# pPump1.net
KiCad netlist of a schematic drawn in EAGLE
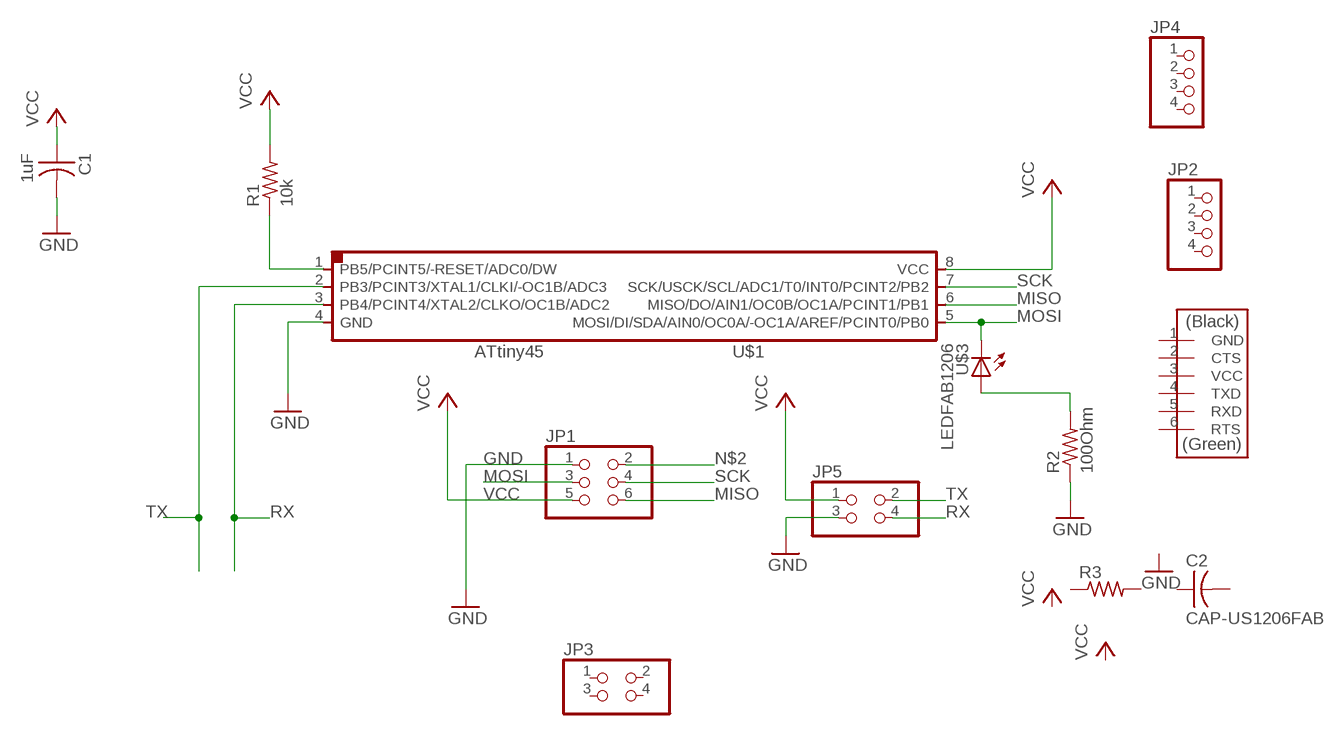
[diagram p0: schematic, sheet 1]

(export (version "E")
  (design (tool "Eeschema 10.0.6"))
  (components
    (comp (ref "C1")
      (value "1uF")
      (footprint "eagle-import:C1206FAB")
      (libsource (lib "eagle-import") (part "CAP-US1206FAB"))
    )
    (comp (ref "C2")
      (value "CAP-US1206FAB")
      (footprint "eagle-import:C1206FAB")
      (libsource (lib "eagle-import") (part "CAP-US1206FAB"))
    )
    (comp (ref "JP1")
      (value "PINHD-2X3-SMD")
      (footprint "eagle-import:2X03SMD")
      (libsource (lib "eagle-import") (part "PINHD-2X3-SMD"))
    )
    (comp (ref "JP2")
      (value "PINHD-1X4")
      (footprint "eagle-import:1X04")
      (libsource (lib "eagle-import") (part "PINHD-1X4"))
    )
    (comp (ref "JP3")
      (value "PINHD-2X2")
      (footprint "eagle-import:2X02")
      (libsource (lib "eagle-import") (part "PINHD-2X2"))
    )
    (comp (ref "JP4")
      (value "PINHD-1X4/90")
      (footprint "eagle-import:1X04_90")
      (libsource (lib "eagle-import") (part "PINHD-1X4/90"))
    )
    (comp (ref "JP5")
      (value "PINHD-2X02_2.54-SMD")
      (footprint "eagle-import:2X02SMD")
      (libsource (lib "eagle-import") (part "PINHD-2X02_2.54-SMD"))
    )
    (comp (ref "R1")
      (value "10k")
      (footprint "eagle-import:R1206FAB")
      (libsource (lib "eagle-import") (part "RES-US1206FAB"))
    )
    (comp (ref "R2")
      (value "100Ohm")
      (footprint "eagle-import:R1206FAB")
      (libsource (lib "eagle-import") (part "RES-US1206FAB"))
    )
    (comp (ref "R3")
      (value "RES-US1206FAB")
      (footprint "eagle-import:R1206FAB")
      (libsource (lib "eagle-import") (part "RES-US1206FAB"))
    )
    (comp (ref "U$1")
      (value "ATTINY45SI")
      (footprint "eagle-import:SOIC8")
      (libsource (lib "eagle-import") (part "ATTINY45SI"))
    )
    (comp (ref "U$2")
      (value "FTDI-SMD-HEADER")
      (footprint "eagle-import:1X06SMD")
      (libsource (lib "eagle-import") (part "FTDI-SMD-HEADER"))
    )
    (comp (ref "U$3")
      (value "LEDFAB1206")
      (footprint "eagle-import:LED1206FAB")
      (libsource (lib "eagle-import") (part "LEDFAB1206"))
    )
  )
  (nets
    (net (code "1") (name "/MISO") (class "Default")
      (node (ref "JP1") (pin "6") (pinfunction "6_6") (pintype "passive"))
      (node (ref "U$1") (pin "6") (pinfunction "MISO/DO/AIN1/OC0B/OC1A/PCINT1/PB1_6") (pintype "bidirectional"))
    )
    (net (code "2") (name "/MOSI") (class "Default")
      (node (ref "JP1") (pin "3") (pinfunction "3_3") (pintype "passive"))
      (node (ref "U$1") (pin "5") (pinfunction "MOSI/DI/SDA/AIN0/OC0A/-OC1A/AREF/PCINT0/PB0_5") (pintype "bidirectional"))
      (node (ref "U$3") (pin "2") (pinfunction "C_2") (pintype "passive"))
    )
    (net (code "3") (name "/N$2") (class "Default")
      (node (ref "JP1") (pin "2") (pinfunction "2_2") (pintype "passive"))
    )
    (net (code "4") (name "/RX") (class "Default")
      (node (ref "JP5") (pin "4") (pinfunction "4_4") (pintype "passive"))
      (node (ref "U$1") (pin "3") (pinfunction "PB4/PCINT4/XTAL2/CLKO/OC1B/ADC2_3") (pintype "bidirectional"))
    )
    (net (code "5") (name "/SCK") (class "Default")
      (node (ref "JP1") (pin "4") (pinfunction "4_4") (pintype "passive"))
      (node (ref "U$1") (pin "7") (pinfunction "SCK/USCK/SCL/ADC1/T0/INT0/PCINT2/PB2_7") (pintype "bidirectional"))
    )
    (net (code "6") (name "/TX") (class "Default")
      (node (ref "JP5") (pin "2") (pinfunction "2_2") (pintype "passive"))
      (node (ref "U$1") (pin "2") (pinfunction "PB3/PCINT3/XTAL1/CLKI/-OC1B/ADC3_2") (pintype "bidirectional"))
    )
    (net (code "7") (name "GND") (class "Default")
      (node (ref "C1") (pin "2") (pinfunction "2_2") (pintype "passive"))
      (node (ref "JP1") (pin "1") (pinfunction "1_1") (pintype "passive"))
      (node (ref "JP5") (pin "3") (pinfunction "3_3") (pintype "passive"))
      (node (ref "R2") (pin "1") (pinfunction "1_1") (pintype "passive"))
      (node (ref "U$1") (pin "4") (pinfunction "GND_4") (pintype "bidirectional"))
    )
    (net (code "8") (name "Net-(U$1-PB5{slash}PCINT5{slash}-RESET{slash}ADC0{slash}DW)") (class "Default")
      (node (ref "R1") (pin "1") (pinfunction "1_1") (pintype "passive"))
      (node (ref "U$1") (pin "1") (pinfunction "PB5/PCINT5/-RESET/ADC0/DW_1") (pintype "bidirectional"))
    )
    (net (code "9") (name "Net-(U$3-A)") (class "Default")
      (node (ref "R2") (pin "2") (pinfunction "2_2") (pintype "passive"))
      (node (ref "U$3") (pin "1") (pinfunction "A_1") (pintype "passive"))
    )
    (net (code "10") (name "VCC") (class "Default")
      (node (ref "C1") (pin "1") (pinfunction "1_1") (pintype "passive"))
      (node (ref "JP1") (pin "5") (pinfunction "5_5") (pintype "passive"))
      (node (ref "JP5") (pin "1") (pinfunction "1_1") (pintype "passive"))
      (node (ref "R1") (pin "2") (pinfunction "2_2") (pintype "passive"))
      (node (ref "U$1") (pin "8") (pinfunction "VCC_8") (pintype "bidirectional"))
    )
    (net (code "11") (name "unconnected-(C2-Pad1)") (class "Default")
      (node (ref "C2") (pin "1") (pinfunction "1_1") (pintype "passive"))
    )
    (net (code "12") (name "unconnected-(C2-Pad2)") (class "Default")
      (node (ref "C2") (pin "2") (pinfunction "2_2") (pintype "passive"))
    )
    (net (code "13") (name "unconnected-(JP2-Pad1)") (class "Default")
      (node (ref "JP2") (pin "1") (pinfunction "1_1") (pintype "passive"))
    )
    (net (code "14") (name "unconnected-(JP2-Pad2)") (class "Default")
      (node (ref "JP2") (pin "2") (pinfunction "2_2") (pintype "passive"))
    )
    (net (code "15") (name "unconnected-(JP2-Pad3)") (class "Default")
      (node (ref "JP2") (pin "3") (pinfunction "3_3") (pintype "passive"))
    )
    (net (code "16") (name "unconnected-(JP2-Pad4)") (class "Default")
      (node (ref "JP2") (pin "4") (pinfunction "4_4") (pintype "passive"))
    )
    (net (code "17") (name "unconnected-(JP3-Pad1)") (class "Default")
      (node (ref "JP3") (pin "1") (pinfunction "1_1") (pintype "passive"))
    )
    (net (code "18") (name "unconnected-(JP3-Pad2)") (class "Default")
      (node (ref "JP3") (pin "2") (pinfunction "2_2") (pintype "passive"))
    )
    (net (code "19") (name "unconnected-(JP3-Pad3)") (class "Default")
      (node (ref "JP3") (pin "3") (pinfunction "3_3") (pintype "passive"))
    )
    (net (code "20") (name "unconnected-(JP3-Pad4)") (class "Default")
      (node (ref "JP3") (pin "4") (pinfunction "4_4") (pintype "passive"))
    )
    (net (code "21") (name "unconnected-(JP4-Pad1)") (class "Default")
      (node (ref "JP4") (pin "1") (pinfunction "1_1") (pintype "passive"))
    )
    (net (code "22") (name "unconnected-(JP4-Pad2)") (class "Default")
      (node (ref "JP4") (pin "2") (pinfunction "2_2") (pintype "passive"))
    )
    (net (code "23") (name "unconnected-(JP4-Pad3)") (class "Default")
      (node (ref "JP4") (pin "3") (pinfunction "3_3") (pintype "passive"))
    )
    (net (code "24") (name "unconnected-(JP4-Pad4)") (class "Default")
      (node (ref "JP4") (pin "4") (pinfunction "4_4") (pintype "passive"))
    )
    (net (code "25") (name "unconnected-(R3-Pad1)") (class "Default")
      (node (ref "R3") (pin "1") (pinfunction "1_1") (pintype "passive"))
    )
    (net (code "26") (name "unconnected-(R3-Pad2)") (class "Default")
      (node (ref "R3") (pin "2") (pinfunction "2_2") (pintype "passive"))
    )
    (net (code "27") (name "unconnected-(U$2-CTS-Pad2)") (class "Default")
      (node (ref "U$2") (pin "2") (pinfunction "CTS_2") (pintype "bidirectional"))
    )
    (net (code "28") (name "unconnected-(U$2-GND-Pad1)") (class "Default")
      (node (ref "U$2") (pin "1") (pinfunction "GND_1") (pintype "bidirectional"))
    )
    (net (code "29") (name "unconnected-(U$2-RTS-Pad6)") (class "Default")
      (node (ref "U$2") (pin "6") (pinfunction "RTS_6") (pintype "bidirectional"))
    )
    (net (code "30") (name "unconnected-(U$2-RXD-Pad5)") (class "Default")
      (node (ref "U$2") (pin "5") (pinfunction "RXD_5") (pintype "bidirectional"))
    )
    (net (code "31") (name "unconnected-(U$2-TXD-Pad4)") (class "Default")
      (node (ref "U$2") (pin "4") (pinfunction "TXD_4") (pintype "bidirectional"))
    )
    (net (code "32") (name "unconnected-(U$2-VCC-Pad3)") (class "Default")
      (node (ref "U$2") (pin "3") (pinfunction "VCC_3") (pintype "bidirectional"))
    )
  )
)
